# 2_MCU.net
KiCad netlist of a schematic drawn in Altium Designer
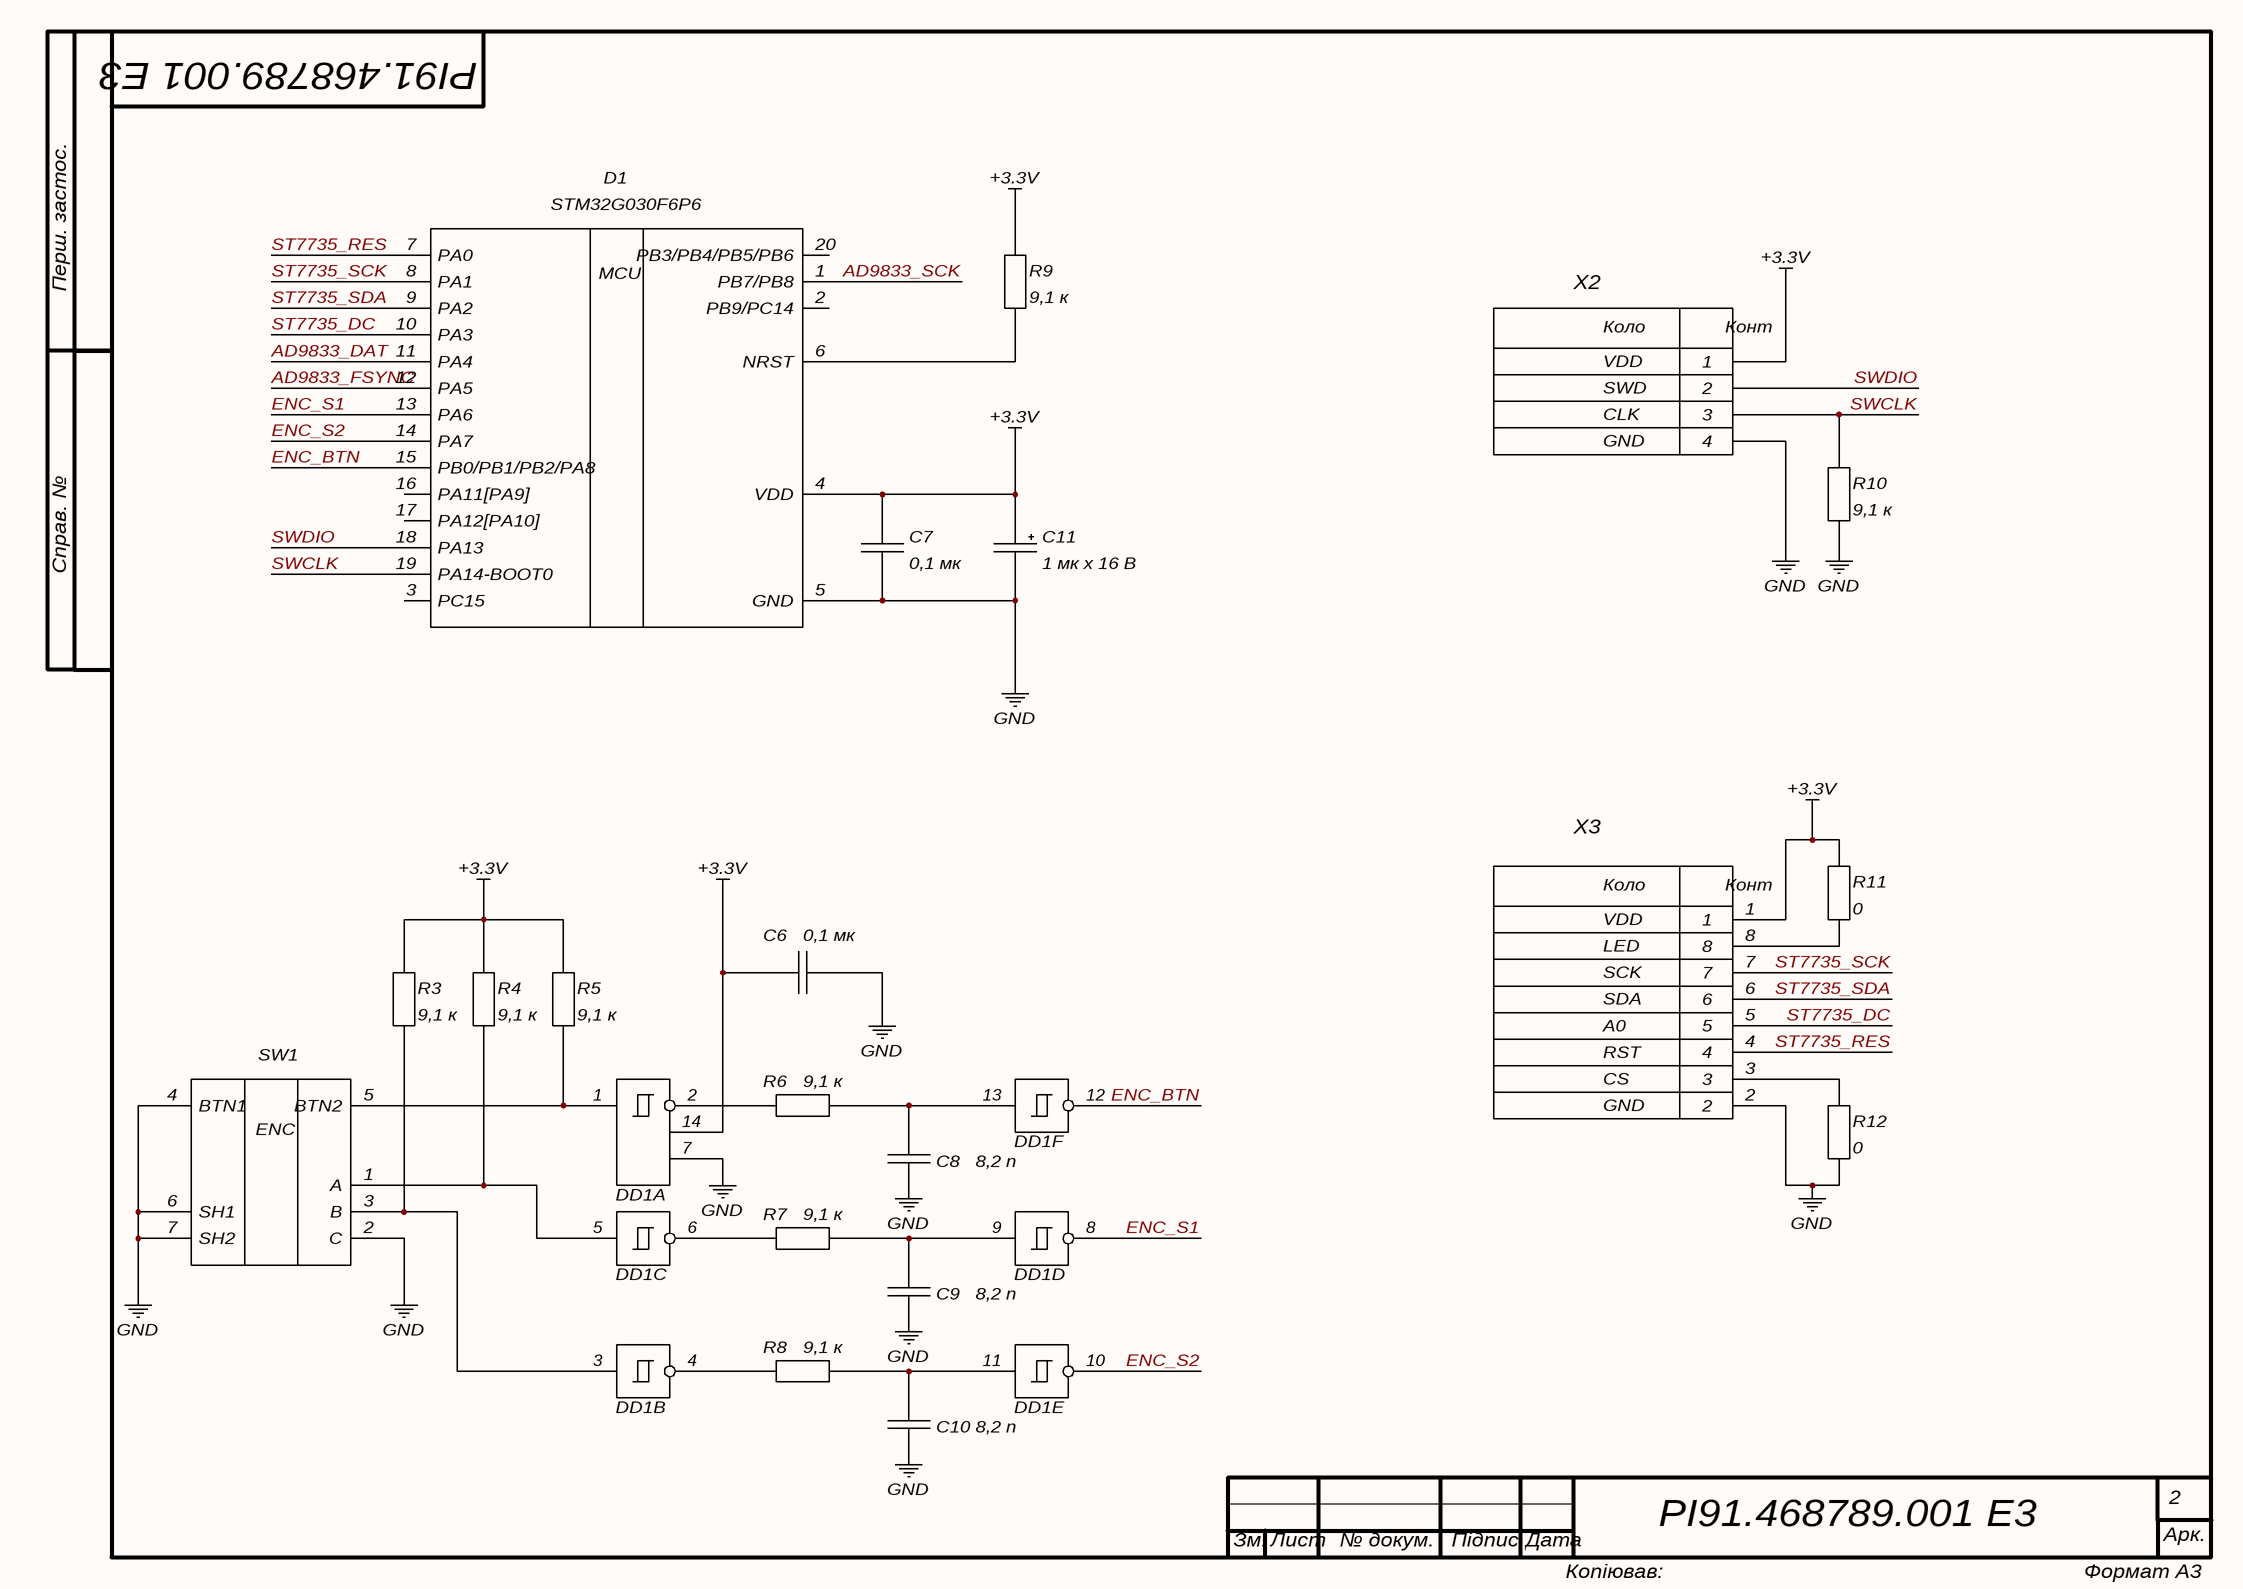
[diagram p0: 2_MCU.SchDoc]

(export (version "E")
  (design (tool "Eeschema 10.0.6"))
  (components
    (comp (ref "C6")
      (value "0.1u")
      (footprint "CAP: 0603")
      (description "Non-polarity")
      (fields (field (name "0,1 МК") "0,1 мк"))
      (libsource (lib "DDS_Generator") (part "Capacitor"))
    )
    (comp (ref "C7")
      (value "0.1u")
      (footprint "CAP: 0603")
      (description "Non-polarity")
      (fields (field (name "0,1 МК") "0,1 мк"))
      (libsource (lib "DDS_Generator") (part "Capacitor"))
    )
    (comp (ref "C8")
      (value "8.2p")
      (footprint "CAP: 0603")
      (description "Non-polarity")
      (fields (field (name "8,2 П") "8,2 п"))
      (libsource (lib "DDS_Generator") (part "Capacitor"))
    )
    (comp (ref "C9")
      (value "8.2p")
      (footprint "CAP: 0603")
      (description "Non-polarity")
      (fields (field (name "8,2 П") "8,2 п"))
      (libsource (lib "DDS_Generator") (part "Capacitor"))
    )
    (comp (ref "C10")
      (value "8.2p")
      (footprint "CAP: 0603")
      (description "Non-polarity")
      (fields (field (name "8,2 П") "8,2 п"))
      (libsource (lib "DDS_Generator") (part "Capacitor"))
    )
    (comp (ref "C11")
      (value "1u 16V")
      (footprint "CAP: TANTAL-A")
      (description "Polarity")
      (fields (field (name "1 16") "1 мк х 16 В"))
      (libsource (lib "DDS_Generator") (part "Capacitor_polar"))
    )
    (comp (ref "D1")
      (value "STM32G030F6P6")
      (footprint "20-TSSOP")
      (description "MCU")
      (fields
        (field (name "MANUFACTURER") "STMicroelectronics")
        (field (name "VALUEMANUFACTURERPARTNUMBER") "IC microcontroller, 32-Bit, Cortex-M0+, 64MHz, 32KB, 8KB, 2...3.6V, -40...+85°C, 20-TSSOP")
        (field (name "PARTNUMBER") "STM32G030F6P6")
      )
      (libsource (lib "DDS_Generator") (part "MCU"))
    )
    (comp (ref "DD1")
      (value "SN74HC14")
      (footprint "14-SOIC")
      (description "Schmitt trigger")
      (libsource (lib "DDS_Generator") (part "SN74HC14"))
    )
    (comp (ref "R3")
      (value "9.1k")
      (footprint "RES: 0603")
      (fields (field (name "9,1 К") "9,1 к"))
      (libsource (lib "") (part "Resistor_2"))
    )
    (comp (ref "R4")
      (value "9.1k")
      (footprint "RES: 0603")
      (fields (field (name "9,1 К") "9,1 к"))
      (libsource (lib "") (part "Resistor_2"))
    )
    (comp (ref "R5")
      (value "9.1k")
      (footprint "RES: 0603")
      (fields (field (name "9,1 К") "9,1 к"))
      (libsource (lib "") (part "Resistor_2"))
    )
    (comp (ref "R6")
      (value "9.1k")
      (footprint "RES: 0603")
      (fields (field (name "9,1 К") "9,1 к"))
      (libsource (lib "") (part "Resistor_1"))
    )
    (comp (ref "R7")
      (value "9.1k")
      (footprint "RES: 0603")
      (fields (field (name "9,1 К") "9,1 к"))
      (libsource (lib "") (part "Resistor_1"))
    )
    (comp (ref "R8")
      (value "9.1k")
      (footprint "RES: 0603")
      (fields (field (name "9,1 К") "9,1 к"))
      (libsource (lib "") (part "Resistor_1"))
    )
    (comp (ref "R9")
      (value "9.1k")
      (footprint "RES: 0603")
      (fields (field (name "9,1 К") "9,1 к"))
      (libsource (lib "") (part "Resistor_2"))
    )
    (comp (ref "R10")
      (value "9.1k")
      (footprint "RES: 0603")
      (fields (field (name "9,1 К") "9,1 к"))
      (libsource (lib "") (part "Resistor_2"))
    )
    (comp (ref "R11")
      (value "0")
      (footprint "RES: 0603")
      (fields (field (name "0") "0"))
      (libsource (lib "DDS_Generator") (part "Resistor"))
    )
    (comp (ref "R12")
      (value "0")
      (footprint "RES: 0603")
      (fields (field (name "0") "0"))
      (libsource (lib "DDS_Generator") (part "Resistor"))
    )
    (comp (ref "SW1")
      (value "EC11")
      (footprint "ENC: EC11")
      (description "Rotary Encoder")
      (libsource (lib "DDS_Generator") (part "Encoder"))
    )
    (comp (ref "X2")
      (value "IDC-10MS")
      (footprint "CON: IDC-10MS")
      (description "SWD Interface")
      (libsource (lib "DDS_Generator") (part "Connector SWD"))
    )
    (comp (ref "X3")
      (value "ST7735 display")
      (footprint "TFT: 1.8 DISPLAY")
      (description "TFT Display")
      (libsource (lib "DDS_Generator") (part "Connector Display"))
    )
  )
  (nets
    (net (code "1") (name "+3.3V") (class "Default")
      (node (ref "C11") (pin "1") (pinfunction "1_1") (pintype "passive"))
      (node (ref "C6") (pin "2") (pinfunction "2_2") (pintype "passive"))
      (node (ref "C7") (pin "2") (pinfunction "2_2") (pintype "passive"))
      (node (ref "D1") (pin "4") (pinfunction "VDD_4") (pintype "power_in"))
      (node (ref "DD1") (pin "14") (pinfunction "VCC_14") (pintype "power_in"))
      (node (ref "R11") (pin "1") (pinfunction "1_1") (pintype "passive"))
      (node (ref "R3") (pin "2") (pinfunction "2_2") (pintype "passive"))
      (node (ref "R4") (pin "2") (pinfunction "2_2") (pintype "passive"))
      (node (ref "R5") (pin "2") (pinfunction "2_2") (pintype "passive"))
      (node (ref "R9") (pin "2") (pinfunction "2_2") (pintype "passive"))
      (node (ref "X2") (pin "3") (pinfunction "1_3") (pintype "power_in"))
      (node (ref "X3") (pin "1") (pinfunction "1_1") (pintype "power_in"))
    )
    (net (code "2") (name "/AD9833_DAT") (class "Default")
      (node (ref "D1") (pin "11") (pinfunction "PA4_11") (pintype "passive"))
    )
    (net (code "3") (name "/AD9833_FSYNC") (class "Default")
      (node (ref "D1") (pin "12") (pinfunction "PA5_12") (pintype "passive"))
    )
    (net (code "4") (name "/AD9833_SCK") (class "Default")
      (node (ref "D1") (pin "1") (pinfunction "PB7/PB8_1") (pintype "passive"))
    )
    (net (code "5") (name "/ENC_BTN") (class "Default")
      (node (ref "D1") (pin "15") (pinfunction "PB0/PB1/PB2/PA8_15") (pintype "passive"))
      (node (ref "DD1") (pin "12") (pinfunction "12_12") (pintype "passive"))
    )
    (net (code "6") (name "/ENC_S1") (class "Default")
      (node (ref "D1") (pin "13") (pinfunction "PA6_13") (pintype "passive"))
      (node (ref "DD1") (pin "8") (pinfunction "8_8") (pintype "passive"))
    )
    (net (code "7") (name "/ENC_S2") (class "Default")
      (node (ref "D1") (pin "14") (pinfunction "PA7_14") (pintype "passive"))
      (node (ref "DD1") (pin "10") (pinfunction "10_10") (pintype "passive"))
    )
    (net (code "8") (name "/ST7735_DC") (class "Default")
      (node (ref "D1") (pin "10") (pinfunction "PA3_10") (pintype "passive"))
      (node (ref "X3") (pin "5") (pinfunction "5_5") (pintype "passive"))
    )
    (net (code "9") (name "/ST7735_RES") (class "Default")
      (node (ref "D1") (pin "7") (pinfunction "PA0_7") (pintype "passive"))
      (node (ref "X3") (pin "4") (pinfunction "4_4") (pintype "passive"))
    )
    (net (code "10") (name "/ST7735_SCK") (class "Default")
      (node (ref "D1") (pin "8") (pinfunction "PA1_8") (pintype "passive"))
      (node (ref "X3") (pin "7") (pinfunction "7_7") (pintype "passive"))
    )
    (net (code "11") (name "/ST7735_SDA") (class "Default")
      (node (ref "D1") (pin "9") (pinfunction "PA2_9") (pintype "passive"))
      (node (ref "X3") (pin "6") (pinfunction "6_6") (pintype "passive"))
    )
    (net (code "12") (name "/SWCLK") (class "Default")
      (node (ref "D1") (pin "19") (pinfunction "PA14-BOOT0_19") (pintype "passive"))
      (node (ref "R10") (pin "2") (pinfunction "2_2") (pintype "passive"))
      (node (ref "X2") (pin "5") (pinfunction "3_5") (pintype "passive"))
    )
    (net (code "13") (name "/SWDIO") (class "Default")
      (node (ref "D1") (pin "18") (pinfunction "PA13_18") (pintype "passive"))
      (node (ref "X2") (pin "9") (pinfunction "2_9") (pintype "passive"))
    )
    (net (code "14") (name "GND") (class "Default")
      (node (ref "C10") (pin "1") (pinfunction "1_1") (pintype "passive"))
      (node (ref "C11") (pin "2") (pinfunction "2_2") (pintype "passive"))
      (node (ref "C6") (pin "1") (pinfunction "1_1") (pintype "passive"))
      (node (ref "C7") (pin "1") (pinfunction "1_1") (pintype "passive"))
      (node (ref "C8") (pin "1") (pinfunction "1_1") (pintype "passive"))
      (node (ref "C9") (pin "1") (pinfunction "1_1") (pintype "passive"))
      (node (ref "D1") (pin "5") (pinfunction "GND_5") (pintype "power_in"))
      (node (ref "DD1") (pin "7") (pinfunction "GND_7") (pintype "power_in"))
      (node (ref "R10") (pin "1") (pinfunction "1_1") (pintype "passive"))
      (node (ref "R12") (pin "2") (pinfunction "2_2") (pintype "passive"))
      (node (ref "SW1") (pin "2") (pinfunction "C_2") (pintype "passive"))
      (node (ref "SW1") (pin "4") (pinfunction "BTN1_4") (pintype "passive"))
      (node (ref "SW1") (pin "6") (pinfunction "SH1_6") (pintype "passive"))
      (node (ref "SW1") (pin "7") (pinfunction "SH2_7") (pintype "passive"))
      (node (ref "X2") (pin "7") (pinfunction "4_7") (pintype "power_in"))
      (node (ref "X3") (pin "2") (pinfunction "2_2") (pintype "power_in"))
    )
    (net (code "15") (name "Net-(C8-Pad2)") (class "Default")
      (node (ref "C8") (pin "2") (pinfunction "2_2") (pintype "passive"))
      (node (ref "DD1") (pin "13") (pinfunction "13_13") (pintype "passive"))
      (node (ref "R6") (pin "2") (pinfunction "2_2") (pintype "passive"))
    )
    (net (code "16") (name "Net-(C9-Pad2)") (class "Default")
      (node (ref "C9") (pin "2") (pinfunction "2_2") (pintype "passive"))
      (node (ref "DD1") (pin "9") (pinfunction "9_9") (pintype "passive"))
      (node (ref "R7") (pin "2") (pinfunction "2_2") (pintype "passive"))
    )
    (net (code "17") (name "Net-(C10-Pad2)") (class "Default")
      (node (ref "C10") (pin "2") (pinfunction "2_2") (pintype "passive"))
      (node (ref "DD1") (pin "11") (pinfunction "11_11") (pintype "passive"))
      (node (ref "R8") (pin "2") (pinfunction "2_2") (pintype "passive"))
    )
    (net (code "18") (name "Net-(D1-NRST)") (class "Default")
      (node (ref "D1") (pin "6") (pinfunction "NRST_6") (pintype "passive"))
      (node (ref "R9") (pin "1") (pinfunction "1_1") (pintype "passive"))
    )
    (net (code "19") (name "Net-(DD1-Pad2)") (class "Default")
      (node (ref "DD1") (pin "2") (pinfunction "2_2") (pintype "passive"))
      (node (ref "R6") (pin "1") (pinfunction "1_1") (pintype "passive"))
    )
    (net (code "20") (name "Net-(DD1-Pad4)") (class "Default")
      (node (ref "DD1") (pin "4") (pinfunction "4_4") (pintype "passive"))
      (node (ref "R8") (pin "1") (pinfunction "1_1") (pintype "passive"))
    )
    (net (code "21") (name "Net-(DD1-Pad6)") (class "Default")
      (node (ref "DD1") (pin "6") (pinfunction "6_6") (pintype "passive"))
      (node (ref "R7") (pin "1") (pinfunction "1_1") (pintype "passive"))
    )
    (net (code "22") (name "Net-(R11-Pad2)") (class "Default")
      (node (ref "R11") (pin "2") (pinfunction "2_2") (pintype "passive"))
      (node (ref "X3") (pin "8") (pinfunction "8_8") (pintype "passive"))
    )
    (net (code "23") (name "Net-(R12-Pad1)") (class "Default")
      (node (ref "R12") (pin "1") (pinfunction "1_1") (pintype "passive"))
      (node (ref "X3") (pin "3") (pinfunction "3_3") (pintype "passive"))
    )
    (net (code "24") (name "Net-(SW1-A)") (class "Default")
      (node (ref "DD1") (pin "5") (pinfunction "5_5") (pintype "passive"))
      (node (ref "R4") (pin "1") (pinfunction "1_1") (pintype "passive"))
      (node (ref "SW1") (pin "1") (pinfunction "A_1") (pintype "passive"))
    )
    (net (code "25") (name "Net-(SW1-B)") (class "Default")
      (node (ref "DD1") (pin "3") (pinfunction "3_3") (pintype "passive"))
      (node (ref "R3") (pin "1") (pinfunction "1_1") (pintype "passive"))
      (node (ref "SW1") (pin "3") (pinfunction "B_3") (pintype "passive"))
    )
    (net (code "26") (name "Net-(SW1-BTN2)") (class "Default")
      (node (ref "DD1") (pin "1") (pinfunction "1_1") (pintype "passive"))
      (node (ref "R5") (pin "1") (pinfunction "1_1") (pintype "passive"))
      (node (ref "SW1") (pin "5") (pinfunction "BTN2_5") (pintype "passive"))
    )
    (net (code "27") (name "unconnected-(D1-PA11[PA9]-Pad16)") (class "Default")
      (node (ref "D1") (pin "16") (pinfunction "PA11[PA9]_16") (pintype "passive"))
    )
    (net (code "28") (name "unconnected-(D1-PA12[PA10]-Pad17)") (class "Default")
      (node (ref "D1") (pin "17") (pinfunction "PA12[PA10]_17") (pintype "passive"))
    )
    (net (code "29") (name "unconnected-(D1-PB3{slash}PB4{slash}PB5{slash}PB6-Pad20)") (class "Default")
      (node (ref "D1") (pin "20") (pinfunction "PB3/PB4/PB5/PB6_20") (pintype "passive"))
    )
    (net (code "30") (name "unconnected-(D1-PB9{slash}PC14-Pad2)") (class "Default")
      (node (ref "D1") (pin "2") (pinfunction "PB9/PC14_2") (pintype "passive"))
    )
    (net (code "31") (name "unconnected-(D1-PC15-Pad3)") (class "Default")
      (node (ref "D1") (pin "3") (pinfunction "PC15_3") (pintype "passive"))
    )
  )
)
